# 39-996_-_SM_Clock-Timer.net
KiCad netlist of a schematic drawn in Altium Designer
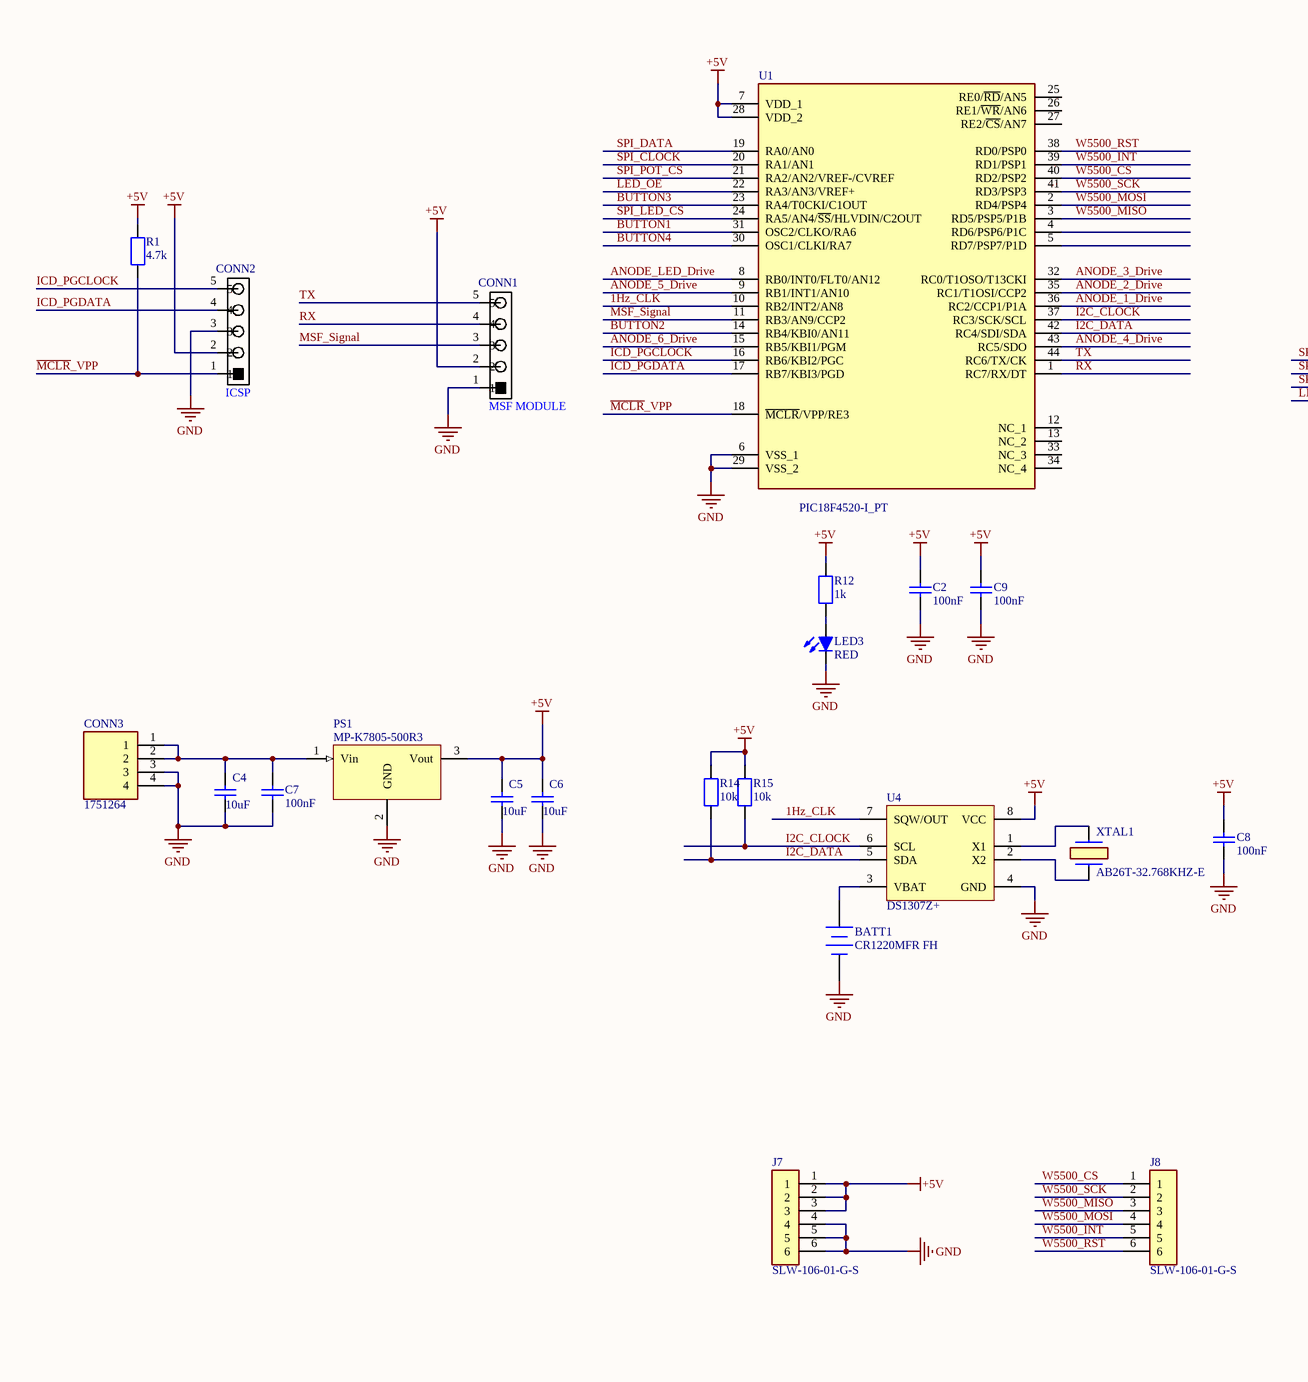
[diagram p0: 39-996 - SM Clock-Timer.SchDoc, left]
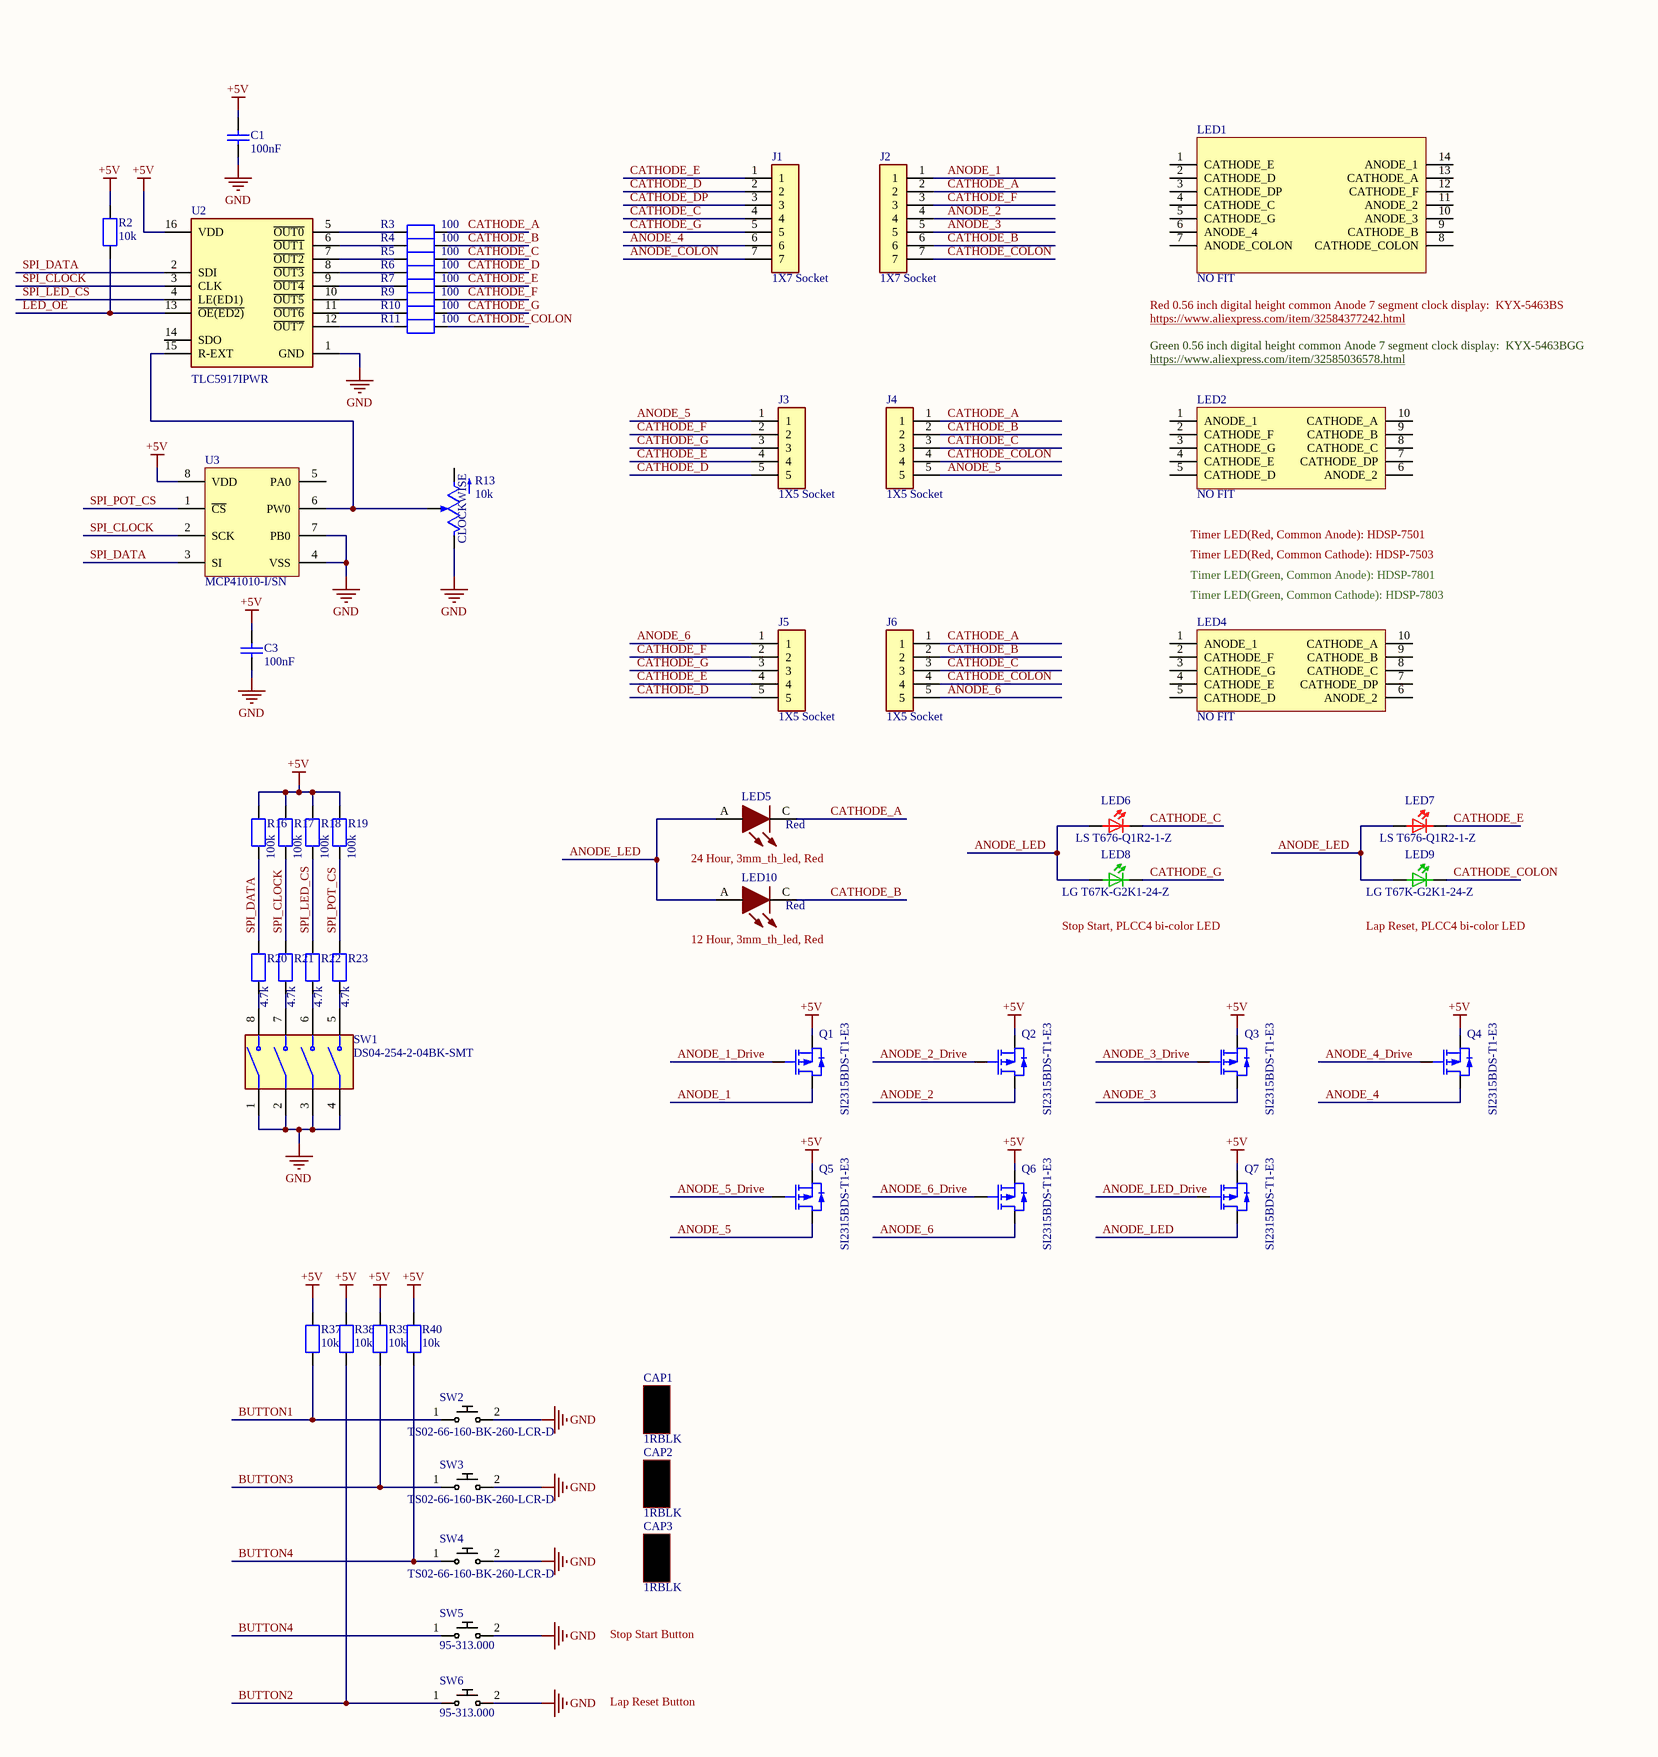
[diagram p1: 39-996 - SM Clock-Timer.SchDoc, right]

(export (version "E")
  (design (tool "Eeschema 10.0.6"))
  (components
    (comp (ref "BATT1")
      (value "CR1220MFR FH")
      (footprint "CR1220MFRFH")
      (description "Coin Cell Battery 3V2-PINHORZ40mAh")
      (fields (field (name "MANUFACTURER") "Renata"))
      (libsource (lib "SM Desk Clock-Timer") (part "CR1220MFR FH"))
    )
    (comp (ref "C1")
      (value "100nF")
      (footprint "C0603")
      (description "100nF ± 10% 50V")
      (fields
        (field (name "MANUFACTURER") "Yageo")
        (field (name "MANUFACTURER PART NUMBER") "CC0603KRX7R9BB104")
      )
      (libsource (lib "Cue Light Output PCB - RJ45") (part "100nF ± 10% 50V"))
    )
    (comp (ref "C2")
      (value "100nF")
      (footprint "C0603")
      (description "100nF ± 10% 50V")
      (fields
        (field (name "MANUFACTURER") "Yageo")
        (field (name "MANUFACTURER PART NUMBER") "CC0603KRX7R9BB104")
      )
      (libsource (lib "Cue Light Output PCB - RJ45") (part "100nF ± 10% 50V"))
    )
    (comp (ref "C3")
      (value "100nF")
      (footprint "C0603")
      (description "100nF ± 10% 50V")
      (fields
        (field (name "MANUFACTURER") "Yageo")
        (field (name "MANUFACTURER PART NUMBER") "CC0603KRX7R9BB104")
      )
      (libsource (lib "Cue Light Output PCB - RJ45") (part "100nF ± 10% 50V"))
    )
    (comp (ref "C4")
      (value "10uF")
      (footprint "C1206")
      (description "10uF ± 10% 50V")
      (fields
        (field (name "MANUFACTURER") "Murata")
        (field (name "MANUFACTURER PART NUMBER") "GRT31CR61H106KE01L")
      )
      (libsource (lib "Cue Light Output PCB - RJ45") (part "10uF ± 10% 50V"))
    )
    (comp (ref "C5")
      (value "10uF")
      (footprint "C1206")
      (description "10uF ± 10% 50V")
      (fields
        (field (name "MANUFACTURER") "Murata")
        (field (name "MANUFACTURER PART NUMBER") "GRT31CR61H106KE01L")
      )
      (libsource (lib "Cue Light Output PCB - RJ45") (part "10uF ± 10% 50V"))
    )
    (comp (ref "C6")
      (value "10uF")
      (footprint "C1206")
      (description "10uF ± 10% 50V")
      (fields
        (field (name "MANUFACTURER") "Murata")
        (field (name "MANUFACTURER PART NUMBER") "GRT31CR61H106KE01L")
      )
      (libsource (lib "Cue Light Output PCB - RJ45") (part "10uF ± 10% 50V"))
    )
    (comp (ref "C7")
      (value "100nF")
      (footprint "C0603")
      (description "100nF ± 10% 50V")
      (fields
        (field (name "MANUFACTURER") "Yageo")
        (field (name "MANUFACTURER PART NUMBER") "CC0603KRX7R9BB104")
      )
      (libsource (lib "Cue Light Output PCB - RJ45") (part "100nF ± 10% 50V"))
    )
    (comp (ref "C8")
      (value "100nF")
      (footprint "C0603")
      (description "100nF ± 10% 50V")
      (fields
        (field (name "MANUFACTURER") "Yageo")
        (field (name "MANUFACTURER PART NUMBER") "CC0603KRX7R9BB104")
      )
      (libsource (lib "Cue Light Output PCB - RJ45") (part "100nF ± 10% 50V"))
    )
    (comp (ref "C9")
      (value "100nF")
      (footprint "C0603")
      (description "100nF ± 10% 50V")
      (fields
        (field (name "MANUFACTURER") "Yageo")
        (field (name "MANUFACTURER PART NUMBER") "CC0603KRX7R9BB104")
      )
      (libsource (lib "Cue Light Output PCB - RJ45") (part "100nF ± 10% 50V"))
    )
    (comp (ref "CAP1")
      (value "1RBLK")
      (footprint "1RBLK")
      (description "Switch Bezels / Switch Caps 9 X 5MM RND CAP BLK")
      (fields (field (name "MANUFACTURER") "E-Switch"))
      (libsource (lib "SM Desk Clock-Timer") (part "1RBLK"))
    )
    (comp (ref "CAP2")
      (value "1RBLK")
      (footprint "1RBLK")
      (description "Switch Bezels / Switch Caps 9 X 5MM RND CAP BLK")
      (fields (field (name "MANUFACTURER") "E-Switch"))
      (libsource (lib "SM Desk Clock-Timer") (part "1RBLK"))
    )
    (comp (ref "CAP3")
      (value "1RBLK")
      (footprint "1RBLK")
      (description "Switch Bezels / Switch Caps 9 X 5MM RND CAP BLK")
      (fields (field (name "MANUFACTURER") "E-Switch"))
      (libsource (lib "SM Desk Clock-Timer") (part "1RBLK"))
    )
    (comp (ref "CONN1")
      (value "NO FIT")
      (footprint "ICSP")
      (description "ICSP Header - 5 Pin, 2.54mm Pitch")
      (libsource (lib "GDS_CONN") (part "ICSP"))
    )
    (comp (ref "CONN2")
      (value "NO FIT")
      (footprint "ICSP")
      (description "ICSP Header - 5 Pin, 2.54mm Pitch")
      (libsource (lib "GDS_CONN") (part "ICSP"))
    )
    (comp (ref "CONN3")
      (value "1751264")
      (footprint "1751264")
      (description "Fixed Terminal Blocks 4P 3.5mm 90DEG")
      (fields (field (name "MANUFACTURER") "Phoenix Contact"))
      (libsource (lib "1751264") (part "1751264"))
    )
    (comp (ref "J1")
      (value "1X7 Socket")
      (footprint "D019970742")
      (description "IC & Component Sockets 7 WAY SIL VERT SKT")
      (fields (field (name "MANUFACTURER") "Harwin") (field (name "MANUFACTURER PART NUMBER") "D01-9970742"))
      (libsource (lib "") (part "D01-9970742_1"))
    )
    (comp (ref "J2")
      (value "1X7 Socket")
      (footprint "D019970742")
      (description "IC & Component Sockets 7 WAY SIL VERT SKT")
      (fields (field (name "MANUFACTURER") "Harwin") (field (name "MANUFACTURER PART NUMBER") "D01-9970742"))
      (libsource (lib "SM Desk Clock-Timer") (part "D01-9970742"))
    )
    (comp (ref "J3")
      (value "1X5 Socket")
      (footprint "D01-9970542")
      (description "IC & Component Sockets 5 WAY SIL VERT SKT")
      (fields (field (name "MANUFACTURER") "Harwin") (field (name "MANUFACTURER PART NUMBER") "D01-9970542"))
      (libsource (lib "SM Desk Clock-Timer") (part "D01-9970542"))
    )
    (comp (ref "J4")
      (value "1X5 Socket")
      (footprint "D01-9970542")
      (description "IC & Component Sockets 5 WAY SIL VERT SKT")
      (fields (field (name "MANUFACTURER") "Harwin") (field (name "MANUFACTURER PART NUMBER") "D01-9970542"))
      (libsource (lib "") (part "D01-9970542_1"))
    )
    (comp (ref "J5")
      (value "1X5 Socket")
      (footprint "D01-9970542")
      (description "IC & Component Sockets 5 WAY SIL VERT SKT")
      (fields (field (name "MANUFACTURER") "Harwin") (field (name "MANUFACTURER PART NUMBER") "D01-9970542"))
      (libsource (lib "SM Desk Clock-Timer") (part "D01-9970542"))
    )
    (comp (ref "J6")
      (value "1X5 Socket")
      (footprint "D01-9970542")
      (description "IC & Component Sockets 5 WAY SIL VERT SKT")
      (fields (field (name "MANUFACTURER") "Harwin") (field (name "MANUFACTURER PART NUMBER") "D01-9970542"))
      (libsource (lib "") (part "D01-9970542_1"))
    )
    (comp (ref "J7")
      (value "SLW-106-01-G-S")
      (footprint "SLW-106-01-G-S")
      (description "Headers & Wire Housings .100\" Tiger Buy Low Profile Socket Strip")
      (fields (field (name "MANUFACTURER") "Samtec"))
      (libsource (lib "SM Desk Clock-Timer") (part "SLW-106-01-G-S"))
    )
    (comp (ref "J8")
      (value "SLW-106-01-G-S")
      (footprint "SLW-106-01-G-S")
      (description "Headers & Wire Housings .100\" Tiger Buy Low Profile Socket Strip")
      (fields (field (name "MANUFACTURER") "Samtec"))
      (libsource (lib "") (part "SLW-106-01-G-S_1"))
    )
    (comp (ref "LED1")
      (value "NO FIT")
      (footprint "Common Cathode 7 Segment Clock Display")
      (description "0.56 inch digit height common Anode 7 segment clock display")
      (libsource (lib "SM Desk Clock-Timer") (part "Common Anode 7 Segment Clock Display"))
    )
    (comp (ref "LED2")
      (value "NO FIT")
      (footprint "HDSP7501")
      (description "7 SEG NUMERIC DISPLAY, HIGH EFFICIENCY RED, 7.6 mm")
      (fields
        (field (name "MANUFACTURER") "Avago Technologies")
        (field (name "MANUFACTURER PART NUMBER") "HDSP-7501")
      )
      (libsource (lib "SM Desk Clock-Timer") (part "HDSP-7501"))
    )
    (comp (ref "LED3")
      (value "RED")
      (footprint "LED_PLCC2")
      (description "Standard LEDs - SMD Super Red, 645nm 180mcd, 20mA")
      (fields
        (field (name "MANUFACTURER") "ams OSRAM")
        (field (name "MANUFACTURER PART NUMBER") "LS T676-Q1R2-1-Z")
      )
      (libsource (lib "Cue Light Output PCB - RJ45") (part "LS T676-Q1R2-1-Z"))
    )
    (comp (ref "LED4")
      (value "NO FIT")
      (footprint "HDSP7501")
      (description "7 SEG NUMERIC DISPLAY, HIGH EFFICIENCY RED, 7.6 mm")
      (fields
        (field (name "MANUFACTURER") "Avago Technologies")
        (field (name "MANUFACTURER PART NUMBER") "HDSP-7501")
      )
      (libsource (lib "SM Desk Clock-Timer") (part "HDSP-7501"))
    )
    (comp (ref "LED5")
      (value "Red")
      (footprint "LED_3mm")
      (description "Standard LEDs - Through Hole RED DIFFUSED")
      (fields (field (name "MANUFACTURER") "Kingbright") (field (name "MANUFACTURER PART NUMBER") "WP132XID"))
      (libsource (lib "SM Desk Clock-Timer") (part "WP132XID"))
    )
    (comp (ref "LED6")
      (value "LS T676-Q1R2-1-Z")
      (footprint "PLCC-2")
      (description "Standard LEDs - SMD Super Red, 645nm 180mcd, 20mA")
      (fields (field (name "MANUFACTURER") "ams OSRAM"))
      (libsource (lib "47-538 - Desk Power CTRL Button") (part "LS T676-Q1R2-1-Z"))
    )
    (comp (ref "LED7")
      (value "LS T676-Q1R2-1-Z")
      (footprint "PLCC-2")
      (description "Standard LEDs - SMD Super Red, 645nm 180mcd, 20mA")
      (fields (field (name "MANUFACTURER") "ams OSRAM"))
      (libsource (lib "47-538 - Desk Power CTRL Button") (part "LS T676-Q1R2-1-Z"))
    )
    (comp (ref "LED8")
      (value "LG T67K-G2K1-24-Z")
      (footprint "PLCC-2")
      (description "Standard LEDs - SMD Green 570nm, 20mA")
      (fields (field (name "MANUFACTURER") "ams OSRAM"))
      (libsource (lib "47-538 - Desk Power CTRL Button") (part "LG T67K-G2K1-24-Z"))
    )
    (comp (ref "LED9")
      (value "LG T67K-G2K1-24-Z")
      (footprint "PLCC-2")
      (description "Standard LEDs - SMD Green 570nm, 20mA")
      (fields (field (name "MANUFACTURER") "ams OSRAM"))
      (libsource (lib "47-538 - Desk Power CTRL Button") (part "LG T67K-G2K1-24-Z"))
    )
    (comp (ref "LED10")
      (value "Red")
      (footprint "LED_3mm")
      (description "Standard LEDs - Through Hole RED DIFFUSED")
      (fields (field (name "MANUFACTURER") "Kingbright") (field (name "MANUFACTURER PART NUMBER") "WP132XID"))
      (libsource (lib "SM Desk Clock-Timer") (part "WP132XID"))
    )
    (comp (ref "PS1")
      (value "MP-K7805-500R3")
      (footprint "CONV_K7805-500R3")
      (fields (field (name "MANUFACTURER") "MULTICOMP PRO"))
      (libsource (lib "SM Desk Clock-Timer") (part "MP-K7805-500R3"))
    )
    (comp (ref "Q1")
      (value "SI2315BDS-T1-E3")
      (footprint "SOT23-3")
      (description "MOSFET 1.8V 3.2A 1.25W")
      (fields (field (name "MANUFACTURER") "Vishay Semiconductors"))
      (libsource (lib "SM Desk Clock-Timer") (part "SI2315BDS-T1-E3"))
    )
    (comp (ref "Q2")
      (value "SI2315BDS-T1-E3")
      (footprint "SOT23-3")
      (description "MOSFET 1.8V 3.2A 1.25W")
      (fields (field (name "MANUFACTURER") "Vishay Semiconductors"))
      (libsource (lib "SM Desk Clock-Timer") (part "SI2315BDS-T1-E3"))
    )
    (comp (ref "Q3")
      (value "SI2315BDS-T1-E3")
      (footprint "SOT23-3")
      (description "MOSFET 1.8V 3.2A 1.25W")
      (fields (field (name "MANUFACTURER") "Vishay Semiconductors"))
      (libsource (lib "SM Desk Clock-Timer") (part "SI2315BDS-T1-E3"))
    )
    (comp (ref "Q4")
      (value "SI2315BDS-T1-E3")
      (footprint "SOT23-3")
      (description "MOSFET 1.8V 3.2A 1.25W")
      (fields (field (name "MANUFACTURER") "Vishay Semiconductors"))
      (libsource (lib "SM Desk Clock-Timer") (part "SI2315BDS-T1-E3"))
    )
    (comp (ref "Q5")
      (value "SI2315BDS-T1-E3")
      (footprint "SOT23-3")
      (description "MOSFET 1.8V 3.2A 1.25W")
      (fields (field (name "MANUFACTURER") "Vishay Semiconductors"))
      (libsource (lib "SM Desk Clock-Timer") (part "SI2315BDS-T1-E3"))
    )
    (comp (ref "Q6")
      (value "SI2315BDS-T1-E3")
      (footprint "SOT23-3")
      (description "MOSFET 1.8V 3.2A 1.25W")
      (fields (field (name "MANUFACTURER") "Vishay Semiconductors"))
      (libsource (lib "SM Desk Clock-Timer") (part "SI2315BDS-T1-E3"))
    )
    (comp (ref "Q7")
      (value "SI2315BDS-T1-E3")
      (footprint "SOT23-3")
      (description "MOSFET 1.8V 3.2A 1.25W")
      (fields (field (name "MANUFACTURER") "Vishay Semiconductors"))
      (libsource (lib "SM Desk Clock-Timer") (part "SI2315BDS-T1-E3"))
    )
    (comp (ref "R1")
      (value "4.7k")
      (footprint "R0603")
      (description "4.7 kOhms ±1% 0.1W")
      (fields
        (field (name "MANUFACTURER") "Yageo")
        (field (name "MANUFACTURER PART NUMBER") "RC0603FR-074K7L")
      )
      (libsource (lib "32-503 - DriveHUB - 1Ch 10A Variable CV") (part "4.7 kOhms ±1% 0.1W"))
    )
    (comp (ref "R2")
      (value "10k")
      (footprint "R0603")
      (description "10 kOhms ±1% 0.1W")
      (fields
        (field (name "MANUFACTURER") "Yageo")
        (field (name "MANUFACTURER PART NUMBER") "RC0603FR-0710KL")
      )
      (libsource (lib "SM Desk Clock-Timer") (part "10 kOhms ±1% 0.1W"))
    )
    (comp (ref "R3")
      (value "100")
      (footprint "R0603")
      (description "100 Ohms ±1% 0.1W")
      (fields
        (field (name "MANUFACTURER") "Yageo")
        (field (name "MANUFACTURER PART NUMBER") "RC0603FR-07100RL")
      )
      (libsource (lib "SM Desk Clock-Timer") (part "100 Ohms ±1% 0.1W"))
    )
    (comp (ref "R4")
      (value "100")
      (footprint "R0603")
      (description "100 Ohms ±1% 0.1W")
      (fields
        (field (name "MANUFACTURER") "Yageo")
        (field (name "MANUFACTURER PART NUMBER") "RC0603FR-07100RL")
      )
      (libsource (lib "SM Desk Clock-Timer") (part "100 Ohms ±1% 0.1W"))
    )
    (comp (ref "R5")
      (value "100")
      (footprint "R0603")
      (description "100 Ohms ±1% 0.1W")
      (fields
        (field (name "MANUFACTURER") "Yageo")
        (field (name "MANUFACTURER PART NUMBER") "RC0603FR-07100RL")
      )
      (libsource (lib "SM Desk Clock-Timer") (part "100 Ohms ±1% 0.1W"))
    )
    (comp (ref "R6")
      (value "100")
      (footprint "R0603")
      (description "100 Ohms ±1% 0.1W")
      (fields
        (field (name "MANUFACTURER") "Yageo")
        (field (name "MANUFACTURER PART NUMBER") "RC0603FR-07100RL")
      )
      (libsource (lib "SM Desk Clock-Timer") (part "100 Ohms ±1% 0.1W"))
    )
    (comp (ref "R7")
      (value "100")
      (footprint "R0603")
      (description "100 Ohms ±1% 0.1W")
      (fields
        (field (name "MANUFACTURER") "Yageo")
        (field (name "MANUFACTURER PART NUMBER") "RC0603FR-07100RL")
      )
      (libsource (lib "SM Desk Clock-Timer") (part "100 Ohms ±1% 0.1W"))
    )
    (comp (ref "R9")
      (value "100")
      (footprint "R0603")
      (description "100 Ohms ±1% 0.1W")
      (fields
        (field (name "MANUFACTURER") "Yageo")
        (field (name "MANUFACTURER PART NUMBER") "RC0603FR-07100RL")
      )
      (libsource (lib "SM Desk Clock-Timer") (part "100 Ohms ±1% 0.1W"))
    )
    (comp (ref "R10")
      (value "100")
      (footprint "R0603")
      (description "100 Ohms ±1% 0.1W")
      (fields
        (field (name "MANUFACTURER") "Yageo")
        (field (name "MANUFACTURER PART NUMBER") "RC0603FR-07100RL")
      )
      (libsource (lib "SM Desk Clock-Timer") (part "100 Ohms ±1% 0.1W"))
    )
    (comp (ref "R11")
      (value "100")
      (footprint "R0603")
      (description "100 Ohms ±1% 0.1W")
      (fields
        (field (name "MANUFACTURER") "Yageo")
        (field (name "MANUFACTURER PART NUMBER") "RC0603FR-07100RL")
      )
      (libsource (lib "SM Desk Clock-Timer") (part "100 Ohms ±1% 0.1W"))
    )
    (comp (ref "R12")
      (value "1k")
      (footprint "R0603")
      (description "1 kOhms ±1% 0.1W")
      (fields
        (field (name "MANUFACTURER") "Yageo")
        (field (name "MANUFACTURER PART NUMBER") "RC0603FR-071KL")
      )
      (libsource (lib "SM Desk Clock-Timer") (part "1 kOhms ±1% 0.1W"))
    )
    (comp (ref "R13")
      (value "10k")
      (footprint "TRIM_3386F-1-103LF")
      (description "Trimmer Resistors - Through Hole 3/8\" 10Kohms 10% 0.5Watts Square")
      (fields
        (field (name "MANUFACTURER") "Bourns")
        (field (name "MANUFACTURER PART NUMBER") "3386F-1-103LF")
      )
      (libsource (lib "SM Desk Clock-Timer") (part "3386F-1-103LF"))
    )
    (comp (ref "R14")
      (value "10k")
      (footprint "R0603")
      (description "10 kOhms ±1% 0.1W")
      (fields
        (field (name "MANUFACTURER") "Yageo")
        (field (name "MANUFACTURER PART NUMBER") "RC0603FR-0710KL")
      )
      (libsource (lib "SM Desk Clock-Timer") (part "10 kOhms ±1% 0.1W"))
    )
    (comp (ref "R15")
      (value "10k")
      (footprint "R0603")
      (description "10 kOhms ±1% 0.1W")
      (fields
        (field (name "MANUFACTURER") "Yageo")
        (field (name "MANUFACTURER PART NUMBER") "RC0603FR-0710KL")
      )
      (libsource (lib "SM Desk Clock-Timer") (part "10 kOhms ±1% 0.1W"))
    )
    (comp (ref "R16")
      (value "100k")
      (footprint "R0603")
      (description "100 kOhms ±1% 0.1W")
      (fields
        (field (name "MANUFACTURER") "Yageo")
        (field (name "MANUFACTURER PART NUMBER") "RC0603FR-07100KL")
      )
      (libsource (lib "SM Desk Clock-Timer") (part "100 kOhms ±1% 0.1W"))
    )
    (comp (ref "R17")
      (value "100k")
      (footprint "R0603")
      (description "100 kOhms ±1% 0.1W")
      (fields
        (field (name "MANUFACTURER") "Yageo")
        (field (name "MANUFACTURER PART NUMBER") "RC0603FR-07100KL")
      )
      (libsource (lib "SM Desk Clock-Timer") (part "100 kOhms ±1% 0.1W"))
    )
    (comp (ref "R18")
      (value "100k")
      (footprint "R0603")
      (description "100 kOhms ±1% 0.1W")
      (fields
        (field (name "MANUFACTURER") "Yageo")
        (field (name "MANUFACTURER PART NUMBER") "RC0603FR-07100KL")
      )
      (libsource (lib "SM Desk Clock-Timer") (part "100 kOhms ±1% 0.1W"))
    )
    (comp (ref "R19")
      (value "100k")
      (footprint "R0603")
      (description "100 kOhms ±1% 0.1W")
      (fields
        (field (name "MANUFACTURER") "Yageo")
        (field (name "MANUFACTURER PART NUMBER") "RC0603FR-07100KL")
      )
      (libsource (lib "SM Desk Clock-Timer") (part "100 kOhms ±1% 0.1W"))
    )
    (comp (ref "R20")
      (value "4.7k")
      (footprint "R0603")
      (description "4.7 kOhms ±1% 0.1W")
      (fields
        (field (name "MANUFACTURER") "Yageo")
        (field (name "MANUFACTURER PART NUMBER") "RC0603FR-074K7L")
      )
      (libsource (lib "32-503 - DriveHUB - 1Ch 10A Variable CV") (part "4.7 kOhms ±1% 0.1W"))
    )
    (comp (ref "R21")
      (value "4.7k")
      (footprint "R0603")
      (description "4.7 kOhms ±1% 0.1W")
      (fields
        (field (name "MANUFACTURER") "Yageo")
        (field (name "MANUFACTURER PART NUMBER") "RC0603FR-074K7L")
      )
      (libsource (lib "32-503 - DriveHUB - 1Ch 10A Variable CV") (part "4.7 kOhms ±1% 0.1W"))
    )
    (comp (ref "R22")
      (value "4.7k")
      (footprint "R0603")
      (description "4.7 kOhms ±1% 0.1W")
      (fields
        (field (name "MANUFACTURER") "Yageo")
        (field (name "MANUFACTURER PART NUMBER") "RC0603FR-074K7L")
      )
      (libsource (lib "32-503 - DriveHUB - 1Ch 10A Variable CV") (part "4.7 kOhms ±1% 0.1W"))
    )
    (comp (ref "R23")
      (value "4.7k")
      (footprint "R0603")
      (description "4.7 kOhms ±1% 0.1W")
      (fields
        (field (name "MANUFACTURER") "Yageo")
        (field (name "MANUFACTURER PART NUMBER") "RC0603FR-074K7L")
      )
      (libsource (lib "32-503 - DriveHUB - 1Ch 10A Variable CV") (part "4.7 kOhms ±1% 0.1W"))
    )
    (comp (ref "R37")
      (value "10k")
      (footprint "R0603")
      (description "10 kOhms ±1% 0.1W")
      (fields
        (field (name "MANUFACTURER") "Yageo")
        (field (name "MANUFACTURER PART NUMBER") "RC0603FR-0710KL")
      )
      (libsource (lib "SM Desk Clock-Timer") (part "10 kOhms ±1% 0.1W"))
    )
    (comp (ref "R38")
      (value "10k")
      (footprint "R0603")
      (description "10 kOhms ±1% 0.1W")
      (fields
        (field (name "MANUFACTURER") "Yageo")
        (field (name "MANUFACTURER PART NUMBER") "RC0603FR-0710KL")
      )
      (libsource (lib "SM Desk Clock-Timer") (part "10 kOhms ±1% 0.1W"))
    )
    (comp (ref "R39")
      (value "10k")
      (footprint "R0603")
      (description "10 kOhms ±1% 0.1W")
      (fields
        (field (name "MANUFACTURER") "Yageo")
        (field (name "MANUFACTURER PART NUMBER") "RC0603FR-0710KL")
      )
      (libsource (lib "SM Desk Clock-Timer") (part "10 kOhms ±1% 0.1W"))
    )
    (comp (ref "R40")
      (value "10k")
      (footprint "R0603")
      (description "10 kOhms ±1% 0.1W")
      (fields
        (field (name "MANUFACTURER") "Yageo")
        (field (name "MANUFACTURER PART NUMBER") "RC0603FR-0710KL")
      )
      (libsource (lib "SM Desk Clock-Timer") (part "10 kOhms ±1% 0.1W"))
    )
    (comp (ref "SW1")
      (value "DS04-254-2-04BK-SMT")
      (footprint "SW_DS04-254-2-04BK-SMT")
      (description "DIP Switches/SIP Switches DIP Switch, SPST, 2.54 pitch, flat actuator, SMT, 4 position, Black")
      (fields (field (name "MANUFACTURER") "CUI Devices"))
      (libsource (lib "SM Desk Clock-Timer") (part "DS04-254-2-04BK-SMT"))
    )
    (comp (ref "SW2")
      (value "TS02-66-160-BK-260-LCR-D")
      (footprint "SW_TS02-66-160-BK-260-LCR-D")
      (description "Tactile Switches 6 x 6 mm, 16 mm Act Height, 260 gf, Black, Long Crimped, Through Hole, SPST,")
      (fields (field (name "MANUFACTURER") "CUI Devices"))
      (libsource (lib "SM Desk Clock-Timer") (part "TS02-66-160-BK-260-LCR-D"))
    )
    (comp (ref "SW3")
      (value "TS02-66-160-BK-260-LCR-D")
      (footprint "SW_TS02-66-160-BK-260-LCR-D")
      (description "Tactile Switches 6 x 6 mm, 16 mm Act Height, 260 gf, Black, Long Crimped, Through Hole, SPST,")
      (fields (field (name "MANUFACTURER") "CUI Devices"))
      (libsource (lib "SM Desk Clock-Timer") (part "TS02-66-160-BK-260-LCR-D"))
    )
    (comp (ref "SW4")
      (value "TS02-66-160-BK-260-LCR-D")
      (footprint "SW_TS02-66-160-BK-260-LCR-D")
      (description "Tactile Switches 6 x 6 mm, 16 mm Act Height, 260 gf, Black, Long Crimped, Through Hole, SPST,")
      (fields (field (name "MANUFACTURER") "CUI Devices"))
      (libsource (lib "SM Desk Clock-Timer") (part "TS02-66-160-BK-260-LCR-D"))
    )
    (comp (ref "SW5")
      (value "95-313.000")
      (footprint "PUSHBUTTON_95-313.000")
      (description "Switching element square, 12.7 x 12.7 mm")
      (fields (field (name "MANUFACTURER") "eao"))
      (libsource (lib "47-538 - Desk Power CTRL Button") (part "95-313.000"))
    )
    (comp (ref "SW6")
      (value "95-313.000")
      (footprint "PUSHBUTTON_95-313.000")
      (description "Switching element square, 12.7 x 12.7 mm")
      (fields (field (name "MANUFACTURER") "eao"))
      (libsource (lib "47-538 - Desk Power CTRL Button") (part "95-313.000"))
    )
    (comp (ref "U1")
      (value "PIC18F4520-I_PT")
      (footprint "TQFP-44")
      (description "MCU 32 KB Flash,1536 RAM, 36 I/O")
      (fields
        (field (name "MANUFACTURER") "Microchip")
        (field (name "MANUFACTURER PART NUMBER") "PIC18F4520-I/PT")
      )
      (libsource (lib "SM Desk Clock-Timer") (part "PIC18F4520-I_PT"))
    )
    (comp (ref "U2")
      (value "TLC5917IPWR")
      (footprint "SOIC-16")
      (description "LED Lighting Drivers 8B Constant-Current LED Sink")
      (fields (field (name "MANUFACTURER") "Texas Instruments"))
      (libsource (lib "SM Desk Clock-Timer") (part "TLC5917IPWR"))
    )
    (comp (ref "U3")
      (value "MCP41010-I/SN")
      (footprint "SOIC-8")
      (description "Digital Potentiometer 10K 256pos SPI SO8")
      (fields (field (name "MANUFACTURER") "Microchip"))
      (libsource (lib "SM Desk Clock-Timer") (part "MCP41010-I/SN"))
    )
    (comp (ref "U4")
      (value "DS1307Z+")
      (footprint "SOIC-8")
      (description "DS1307Z+, Real Time Clock, Alarm, Calendar, Clock, 56B RAM, I2C, 5V, 8-Pin SOIC")
      (fields (field (name "MANUFACTURER") "Analog Devices"))
      (libsource (lib "SM Desk Clock-Timer") (part "DS1307Z+"))
    )
    (comp (ref "XTAL1")
      (value "AB26T-32.768KHZ-E")
      (footprint "AB26T32768KHZE")
      (description "OSC XO 1.33GHZ 2.5V LVPECL")
      (fields (field (name "MANUFACTURER") "ABRACON"))
      (libsource (lib "SM Desk Clock-Timer") (part "AB26T-32.768KHZ-E"))
    )
  )
  (nets
    (net (code "1") (name "+5V") (class "Default")
      (node (ref "C1") (pin "2") (pinfunction "2_2") (pintype "passive"))
      (node (ref "C2") (pin "2") (pinfunction "2_2") (pintype "passive"))
      (node (ref "C3") (pin "2") (pinfunction "2_2") (pintype "passive"))
      (node (ref "C5") (pin "2") (pinfunction "2_2") (pintype "passive"))
      (node (ref "C6") (pin "2") (pinfunction "2_2") (pintype "passive"))
      (node (ref "C8") (pin "2") (pinfunction "2_2") (pintype "passive"))
      (node (ref "C9") (pin "2") (pinfunction "2_2") (pintype "passive"))
      (node (ref "CONN1") (pin "2") (pinfunction "2_2") (pintype "passive"))
      (node (ref "CONN2") (pin "2") (pinfunction "2_2") (pintype "passive"))
      (node (ref "J7") (pin "1") (pinfunction "1_1") (pintype "passive"))
      (node (ref "J7") (pin "2") (pinfunction "2_2") (pintype "passive"))
      (node (ref "J7") (pin "3") (pinfunction "3_3") (pintype "passive"))
      (node (ref "PS1") (pin "3") (pinfunction "Vout_3") (pintype "passive"))
      (node (ref "Q1") (pin "2") (pinfunction "S_2") (pintype "passive"))
      (node (ref "Q2") (pin "2") (pinfunction "S_2") (pintype "passive"))
      (node (ref "Q3") (pin "2") (pinfunction "S_2") (pintype "passive"))
      (node (ref "Q4") (pin "2") (pinfunction "S_2") (pintype "passive"))
      (node (ref "Q5") (pin "2") (pinfunction "S_2") (pintype "passive"))
      (node (ref "Q6") (pin "2") (pinfunction "S_2") (pintype "passive"))
      (node (ref "Q7") (pin "2") (pinfunction "S_2") (pintype "passive"))
      (node (ref "R1") (pin "2") (pinfunction "2_2") (pintype "passive"))
      (node (ref "R12") (pin "2") (pinfunction "2_2") (pintype "passive"))
      (node (ref "R14") (pin "2") (pinfunction "2_2") (pintype "passive"))
      (node (ref "R15") (pin "2") (pinfunction "2_2") (pintype "passive"))
      (node (ref "R16") (pin "2") (pinfunction "2_2") (pintype "passive"))
      (node (ref "R17") (pin "2") (pinfunction "2_2") (pintype "passive"))
      (node (ref "R18") (pin "2") (pinfunction "2_2") (pintype "passive"))
      (node (ref "R19") (pin "2") (pinfunction "2_2") (pintype "passive"))
      (node (ref "R2") (pin "2") (pinfunction "2_2") (pintype "passive"))
      (node (ref "R37") (pin "2") (pinfunction "2_2") (pintype "passive"))
      (node (ref "R38") (pin "2") (pinfunction "2_2") (pintype "passive"))
      (node (ref "R39") (pin "2") (pinfunction "2_2") (pintype "passive"))
      (node (ref "R40") (pin "2") (pinfunction "2_2") (pintype "passive"))
      (node (ref "U1") (pin "28") (pinfunction "VDD_2_28") (pintype "passive"))
      (node (ref "U1") (pin "7") (pinfunction "VDD_1_7") (pintype "passive"))
      (node (ref "U2") (pin "16") (pinfunction "VDD_16") (pintype "passive"))
      (node (ref "U3") (pin "8") (pinfunction "VDD_8") (pintype "passive"))
      (node (ref "U4") (pin "8") (pinfunction "VCC_8") (pintype "passive"))
    )
    (net (code "2") (name "/1Hz_CLK") (class "Default")
      (node (ref "U1") (pin "10") (pinfunction "RB2/INT2/AN8_10") (pintype "passive"))
      (node (ref "U4") (pin "7") (pinfunction "SQW/OUT_7") (pintype "passive"))
    )
    (net (code "3") (name "/ANODE_1") (class "Default")
      (node (ref "J2") (pin "1") (pinfunction "1_1") (pintype "passive"))
      (node (ref "Q1") (pin "3") (pinfunction "D_3") (pintype "passive"))
    )
    (net (code "4") (name "/ANODE_1_Drive") (class "Default")
      (node (ref "Q1") (pin "1") (pinfunction "G_1") (pintype "passive"))
      (node (ref "U1") (pin "36") (pinfunction "RC2/CCP1/P1A_36") (pintype "passive"))
    )
    (net (code "5") (name "/ANODE_2") (class "Default")
      (node (ref "J2") (pin "4") (pinfunction "4_4") (pintype "passive"))
      (node (ref "Q2") (pin "3") (pinfunction "D_3") (pintype "passive"))
    )
    (net (code "6") (name "/ANODE_2_Drive") (class "Default")
      (node (ref "Q2") (pin "1") (pinfunction "G_1") (pintype "passive"))
      (node (ref "U1") (pin "35") (pinfunction "RC1/T1OSI/CCP2_35") (pintype "passive"))
    )
    (net (code "7") (name "/ANODE_3") (class "Default")
      (node (ref "J2") (pin "5") (pinfunction "5_5") (pintype "passive"))
      (node (ref "Q3") (pin "3") (pinfunction "D_3") (pintype "passive"))
    )
    (net (code "8") (name "/ANODE_3_Drive") (class "Default")
      (node (ref "Q3") (pin "1") (pinfunction "G_1") (pintype "passive"))
      (node (ref "U1") (pin "32") (pinfunction "RC0/T1OSO/T13CKI_32") (pintype "passive"))
    )
    (net (code "9") (name "/ANODE_4") (class "Default")
      (node (ref "J1") (pin "6") (pinfunction "6_6") (pintype "passive"))
      (node (ref "Q4") (pin "3") (pinfunction "D_3") (pintype "passive"))
    )
    (net (code "10") (name "/ANODE_4_Drive") (class "Default")
      (node (ref "Q4") (pin "1") (pinfunction "G_1") (pintype "passive"))
      (node (ref "U1") (pin "43") (pinfunction "RC5/SDO_43") (pintype "passive"))
    )
    (net (code "11") (name "/ANODE_5") (class "Default")
      (node (ref "J3") (pin "1") (pinfunction "1_1") (pintype "passive"))
      (node (ref "J4") (pin "5") (pinfunction "5_5") (pintype "passive"))
      (node (ref "Q5") (pin "3") (pinfunction "D_3") (pintype "passive"))
    )
    (net (code "12") (name "/ANODE_5_Drive") (class "Default")
      (node (ref "Q5") (pin "1") (pinfunction "G_1") (pintype "passive"))
      (node (ref "U1") (pin "9") (pinfunction "RB1/INT1/AN10_9") (pintype "passive"))
    )
    (net (code "13") (name "/ANODE_6") (class "Default")
      (node (ref "J5") (pin "1") (pinfunction "1_1") (pintype "passive"))
      (node (ref "J6") (pin "5") (pinfunction "5_5") (pintype "passive"))
      (node (ref "Q6") (pin "3") (pinfunction "D_3") (pintype "passive"))
    )
    (net (code "14") (name "/ANODE_6_Drive") (class "Default")
      (node (ref "Q6") (pin "1") (pinfunction "G_1") (pintype "passive"))
      (node (ref "U1") (pin "15") (pinfunction "RB5/KBI1/PGM_15") (pintype "passive"))
    )
    (net (code "15") (name "/ANODE_COLON") (class "Default")
      (node (ref "J1") (pin "7") (pinfunction "7_7") (pintype "passive"))
    )
    (net (code "16") (name "/ANODE_LED") (class "Default")
      (node (ref "LED10") (pin "A") (pinfunction "A_A") (pintype "passive"))
      (node (ref "LED5") (pin "A") (pinfunction "A_A") (pintype "passive"))
      (node (ref "LED6") (pin "A") (pinfunction "A_A") (pintype "passive"))
      (node (ref "LED7") (pin "A") (pinfunction "A_A") (pintype "passive"))
      (node (ref "LED8") (pin "A") (pinfunction "A_A") (pintype "passive"))
      (node (ref "LED9") (pin "A") (pinfunction "A_A") (pintype "passive"))
      (node (ref "Q7") (pin "3") (pinfunction "D_3") (pintype "passive"))
    )
    (net (code "17") (name "/ANODE_LED_Drive") (class "Default")
      (node (ref "Q7") (pin "1") (pinfunction "G_1") (pintype "passive"))
      (node (ref "U1") (pin "8") (pinfunction "RB0/INT0/FLT0/AN12_8") (pintype "passive"))
    )
    (net (code "18") (name "/BUTTON1") (class "Default")
      (node (ref "R37") (pin "1") (pinfunction "1_1") (pintype "passive"))
      (node (ref "SW2") (pin "1") (pinfunction "1_1") (pintype "passive"))
      (node (ref "U1") (pin "31") (pinfunction "OSC2/CLKO/RA6_31") (pintype "passive"))
    )
    (net (code "19") (name "/BUTTON2") (class "Default")
      (node (ref "R38") (pin "1") (pinfunction "1_1") (pintype "passive"))
      (node (ref "SW6") (pin "1") (pinfunction "1_1") (pintype "passive"))
      (node (ref "U1") (pin "14") (pinfunction "RB4/KBI0/AN11_14") (pintype "passive"))
    )
    (net (code "20") (name "/BUTTON3") (class "Default")
      (node (ref "R39") (pin "1") (pinfunction "1_1") (pintype "passive"))
      (node (ref "SW3") (pin "1") (pinfunction "1_1") (pintype "passive"))
      (node (ref "U1") (pin "23") (pinfunction "RA4/T0CKI/C1OUT_23") (pintype "passive"))
    )
    (net (code "21") (name "/BUTTON4") (class "Default")
      (node (ref "R40") (pin "1") (pinfunction "1_1") (pintype "passive"))
      (node (ref "SW4") (pin "1") (pinfunction "1_1") (pintype "passive"))
      (node (ref "SW5") (pin "1") (pinfunction "1_1") (pintype "passive"))
      (node (ref "U1") (pin "30") (pinfunction "OSC1/CLKI/RA7_30") (pintype "passive"))
    )
    (net (code "22") (name "/CATHODE_A") (class "Default")
      (node (ref "J2") (pin "2") (pinfunction "2_2") (pintype "passive"))
      (node (ref "J4") (pin "1") (pinfunction "1_1") (pintype "passive"))
      (node (ref "J6") (pin "1") (pinfunction "1_1") (pintype "passive"))
      (node (ref "LED5") (pin "C") (pinfunction "C_C") (pintype "passive"))
      (node (ref "R3") (pin "2") (pinfunction "2_2") (pintype "passive"))
    )
    (net (code "23") (name "/CATHODE_B") (class "Default")
      (node (ref "J2") (pin "6") (pinfunction "6_6") (pintype "passive"))
      (node (ref "J4") (pin "2") (pinfunction "2_2") (pintype "passive"))
      (node (ref "J6") (pin "2") (pinfunction "2_2") (pintype "passive"))
      (node (ref "LED10") (pin "C") (pinfunction "C_C") (pintype "passive"))
      (node (ref "R4") (pin "2") (pinfunction "2_2") (pintype "passive"))
    )
    (net (code "24") (name "/CATHODE_C") (class "Default")
      (node (ref "J1") (pin "4") (pinfunction "4_4") (pintype "passive"))
      (node (ref "J4") (pin "3") (pinfunction "3_3") (pintype "passive"))
      (node (ref "J6") (pin "3") (pinfunction "3_3") (pintype "passive"))
      (node (ref "LED6") (pin "C") (pinfunction "C_C") (pintype "passive"))
      (node (ref "R5") (pin "2") (pinfunction "2_2") (pintype "passive"))
    )
    (net (code "25") (name "/CATHODE_COLON") (class "Default")
      (node (ref "J2") (pin "7") (pinfunction "7_7") (pintype "passive"))
      (node (ref "J4") (pin "4") (pinfunction "4_4") (pintype "passive"))
      (node (ref "J6") (pin "4") (pinfunction "4_4") (pintype "passive"))
      (node (ref "LED9") (pin "C") (pinfunction "C_C") (pintype "passive"))
      (node (ref "R11") (pin "2") (pinfunction "2_2") (pintype "passive"))
    )
    (net (code "26") (name "/CATHODE_D") (class "Default")
      (node (ref "J1") (pin "2") (pinfunction "2_2") (pintype "passive"))
      (node (ref "J3") (pin "5") (pinfunction "5_5") (pintype "passive"))
      (node (ref "J5") (pin "5") (pinfunction "5_5") (pintype "passive"))
      (node (ref "R6") (pin "2") (pinfunction "2_2") (pintype "passive"))
    )
    (net (code "27") (name "/CATHODE_DP") (class "Default")
      (node (ref "J1") (pin "3") (pinfunction "3_3") (pintype "passive"))
    )
    (net (code "28") (name "/CATHODE_E") (class "Default")
      (node (ref "J1") (pin "1") (pinfunction "1_1") (pintype "passive"))
      (node (ref "J3") (pin "4") (pinfunction "4_4") (pintype "passive"))
      (node (ref "J5") (pin "4") (pinfunction "4_4") (pintype "passive"))
      (node (ref "LED7") (pin "C") (pinfunction "C_C") (pintype "passive"))
      (node (ref "R7") (pin "2") (pinfunction "2_2") (pintype "passive"))
    )
    (net (code "29") (name "/CATHODE_F") (class "Default")
      (node (ref "J2") (pin "3") (pinfunction "3_3") (pintype "passive"))
      (node (ref "J3") (pin "2") (pinfunction "2_2") (pintype "passive"))
      (node (ref "J5") (pin "2") (pinfunction "2_2") (pintype "passive"))
      (node (ref "R9") (pin "2") (pinfunction "2_2") (pintype "passive"))
    )
    (net (code "30") (name "/CATHODE_G") (class "Default")
      (node (ref "J1") (pin "5") (pinfunction "5_5") (pintype "passive"))
      (node (ref "J3") (pin "3") (pinfunction "3_3") (pintype "passive"))
      (node (ref "J5") (pin "3") (pinfunction "3_3") (pintype "passive"))
      (node (ref "LED8") (pin "C") (pinfunction "C_C") (pintype "passive"))
      (node (ref "R10") (pin "2") (pinfunction "2_2") (pintype "passive"))
    )
    (net (code "31") (name "/I2C_CLOCK") (class "Default")
      (node (ref "R15") (pin "1") (pinfunction "1_1") (pintype "passive"))
      (node (ref "U1") (pin "37") (pinfunction "RC3/SCK/SCL_37") (pintype "passive"))
      (node (ref "U4") (pin "6") (pinfunction "SCL_6") (pintype "passive"))
    )
    (net (code "32") (name "/I2C_DATA") (class "Default")
      (node (ref "R14") (pin "1") (pinfunction "1_1") (pintype "passive"))
      (node (ref "U1") (pin "42") (pinfunction "RC4/SDI/SDA_42") (pintype "passive"))
      (node (ref "U4") (pin "5") (pinfunction "SDA_5") (pintype "passive"))
    )
    (net (code "33") (name "/ICD_PGCLOCK") (class "Default")
      (node (ref "CONN2") (pin "5") (pinfunction "5_5") (pintype "passive"))
      (node (ref "U1") (pin "16") (pinfunction "RB6/KBI2/PGC_16") (pintype "passive"))
    )
    (net (code "34") (name "/ICD_PGDATA") (class "Default")
      (node (ref "CONN2") (pin "4") (pinfunction "4_4") (pintype "passive"))
      (node (ref "U1") (pin "17") (pinfunction "RB7/KBI3/PGD_17") (pintype "passive"))
    )
    (net (code "35") (name "/MSF_Signal") (class "Default")
      (node (ref "CONN1") (pin "3") (pinfunction "3_3") (pintype "passive"))
      (node (ref "U1") (pin "11") (pinfunction "RB3/AN9/CCP2_11") (pintype "passive"))
    )
    (net (code "36") (name "/RX") (class "Default")
      (node (ref "CONN1") (pin "4") (pinfunction "4_4") (pintype "passive"))
      (node (ref "U1") (pin "1") (pinfunction "RC7/RX/DT_1") (pintype "passive"))
    )
    (net (code "37") (name "/SPI_CLOCK") (class "Default")
      (node (ref "R17") (pin "1") (pinfunction "1_1") (pintype "passive"))
      (node (ref "R21") (pin "2") (pinfunction "2_2") (pintype "passive"))
      (node (ref "U1") (pin "20") (pinfunction "RA1/AN1_20") (pintype "passive"))
      (node (ref "U2") (pin "3") (pinfunction "CLK_3") (pintype "passive"))
      (node (ref "U3") (pin "2") (pinfunction "SCK_2") (pintype "passive"))
    )
    (net (code "38") (name "/SPI_DATA") (class "Default")
      (node (ref "R16") (pin "1") (pinfunction "1_1") (pintype "passive"))
      (node (ref "R20") (pin "2") (pinfunction "2_2") (pintype "passive"))
      (node (ref "U1") (pin "19") (pinfunction "RA0/AN0_19") (pintype "passive"))
      (node (ref "U2") (pin "2") (pinfunction "SDI_2") (pintype "passive"))
      (node (ref "U3") (pin "3") (pinfunction "SI_3") (pintype "passive"))
    )
    (net (code "39") (name "/SPI_LED_CS") (class "Default")
      (node (ref "R18") (pin "1") (pinfunction "1_1") (pintype "passive"))
      (node (ref "R22") (pin "2") (pinfunction "2_2") (pintype "passive"))
      (node (ref "U1") (pin "24") (pinfunction "RA5/AN4/~{SS}/HLVDIN/C2OUT_24") (pintype "passive"))
      (node (ref "U2") (pin "4") (pinfunction "LE(ED1)_4") (pintype "passive"))
    )
    (net (code "40") (name "/SPI_POT_CS") (class "Default")
      (node (ref "R19") (pin "1") (pinfunction "1_1") (pintype "passive"))
      (node (ref "R23") (pin "2") (pinfunction "2_2") (pintype "passive"))
      (node (ref "U1") (pin "21") (pinfunction "RA2/AN2/VREF-/CVREF_21") (pintype "passive"))
      (node (ref "U3") (pin "1") (pinfunction "~{CS}_1") (pintype "passive"))
    )
    (net (code "41") (name "/TX") (class "Default")
      (node (ref "CONN1") (pin "5") (pinfunction "5_5") (pintype "passive"))
      (node (ref "U1") (pin "44") (pinfunction "RC6/TX/CK_44") (pintype "passive"))
    )
    (net (code "42") (name "/W5500_CS") (class "Default")
      (node (ref "J8") (pin "1") (pinfunction "1_1") (pintype "passive"))
      (node (ref "U1") (pin "40") (pinfunction "RD2/PSP2_40") (pintype "passive"))
    )
    (net (code "43") (name "/W5500_INT") (class "Default")
      (node (ref "J8") (pin "5") (pinfunction "5_5") (pintype "passive"))
      (node (ref "U1") (pin "39") (pinfunction "RD1/PSP1_39") (pintype "passive"))
    )
    (net (code "44") (name "/W5500_MISO") (class "Default")
      (node (ref "J8") (pin "3") (pinfunction "3_3") (pintype "passive"))
      (node (ref "U1") (pin "3") (pinfunction "RD5/PSP5/P1B_3") (pintype "passive"))
    )
    (net (code "45") (name "/W5500_MOSI") (class "Default")
      (node (ref "J8") (pin "4") (pinfunction "4_4") (pintype "passive"))
      (node (ref "U1") (pin "2") (pinfunction "RD4/PSP4_2") (pintype "passive"))
    )
    (net (code "46") (name "/W5500_RST") (class "Default")
      (node (ref "J8") (pin "6") (pinfunction "6_6") (pintype "passive"))
      (node (ref "U1") (pin "38") (pinfunction "RD0/PSP0_38") (pintype "passive"))
    )
    (net (code "47") (name "/W5500_SCK") (class "Default")
      (node (ref "J8") (pin "2") (pinfunction "2_2") (pintype "passive"))
      (node (ref "U1") (pin "41") (pinfunction "RD3/PSP3_41") (pintype "passive"))
    )
    (net (code "48") (name "/~{LED_OE}") (class "Default")
      (node (ref "R2") (pin "1") (pinfunction "1_1") (pintype "passive"))
      (node (ref "U1") (pin "22") (pinfunction "RA3/AN3/VREF+_22") (pintype "passive"))
      (node (ref "U2") (pin "13") (pinfunction "~{OE(ED2)}_13") (pintype "passive"))
    )
    (net (code "49") (name "/~{MCLR}_VPP") (class "Default")
      (node (ref "CONN2") (pin "1") (pinfunction "1_1") (pintype "passive"))
      (node (ref "R1") (pin "1") (pinfunction "1_1") (pintype "passive"))
      (node (ref "U1") (pin "18") (pinfunction "~{MCLR}/VPP/RE3_18") (pintype "passive"))
    )
    (net (code "50") (name "GND") (class "Default")
      (node (ref "BATT1") (pin "-") (pinfunction "-_-") (pintype "passive"))
      (node (ref "C1") (pin "1") (pinfunction "1_1") (pintype "passive"))
      (node (ref "C2") (pin "1") (pinfunction "1_1") (pintype "passive"))
      (node (ref "C3") (pin "1") (pinfunction "1_1") (pintype "passive"))
      (node (ref "C4") (pin "1") (pinfunction "1_1") (pintype "passive"))
      (node (ref "C5") (pin "1") (pinfunction "1_1") (pintype "passive"))
      (node (ref "C6") (pin "1") (pinfunction "1_1") (pintype "passive"))
      (node (ref "C7") (pin "1") (pinfunction "1_1") (pintype "passive"))
      (node (ref "C8") (pin "1") (pinfunction "1_1") (pintype "passive"))
      (node (ref "C9") (pin "1") (pinfunction "1_1") (pintype "passive"))
      (node (ref "CONN1") (pin "1") (pinfunction "1_1") (pintype "passive"))
      (node (ref "CONN2") (pin "3") (pinfunction "3_3") (pintype "passive"))
      (node (ref "CONN3") (pin "3") (pinfunction "3_3") (pintype "passive"))
      (node (ref "CONN3") (pin "4") (pinfunction "4_4") (pintype "passive"))
      (node (ref "J7") (pin "4") (pinfunction "4_4") (pintype "passive"))
      (node (ref "J7") (pin "5") (pinfunction "5_5") (pintype "passive"))
      (node (ref "J7") (pin "6") (pinfunction "6_6") (pintype "passive"))
      (node (ref "LED3") (pin "1") (pinfunction "1_1") (pintype "passive"))
      (node (ref "PS1") (pin "2") (pinfunction "GND_2") (pintype "passive"))
      (node (ref "R13") (pin "1") (pinfunction "CCW_1") (pintype "passive"))
      (node (ref "SW1") (pin "1") (pinfunction "1_1") (pintype "passive"))
      (node (ref "SW1") (pin "2") (pinfunction "2_2") (pintype "passive"))
      (node (ref "SW1") (pin "3") (pinfunction "3_3") (pintype "passive"))
      (node (ref "SW1") (pin "4") (pinfunction "4_4") (pintype "passive"))
      (node (ref "SW2") (pin "2") (pinfunction "2_2") (pintype "passive"))
      (node (ref "SW3") (pin "2") (pinfunction "2_2") (pintype "passive"))
      (node (ref "SW4") (pin "2") (pinfunction "2_2") (pintype "passive"))
      (node (ref "SW5") (pin "2") (pinfunction "2_2") (pintype "passive"))
      (node (ref "SW6") (pin "2") (pinfunction "2_2") (pintype "passive"))
      (node (ref "U1") (pin "29") (pinfunction "VSS_2_29") (pintype "passive"))
      (node (ref "U1") (pin "6") (pinfunction "VSS_1_6") (pintype "passive"))
      (node (ref "U2") (pin "1") (pinfunction "GND_1") (pintype "passive"))
      (node (ref "U3") (pin "4") (pinfunction "VSS_4") (pintype "passive"))
      (node (ref "U3") (pin "7") (pinfunction "PB0_7") (pintype "passive"))
      (node (ref "U4") (pin "4") (pinfunction "GND_4") (pintype "passive"))
    )
    (net (code "51") (name "Net-(LED3-Pad2)") (class "Default")
      (node (ref "LED3") (pin "2") (pinfunction "2_2") (pintype "passive"))
      (node (ref "R12") (pin "1") (pinfunction "1_1") (pintype "passive"))
    )
    (net (code "52") (name "Net-(PS1-Vin)") (class "Default")
      (node (ref "C4") (pin "2") (pinfunction "2_2") (pintype "passive"))
      (node (ref "C7") (pin "2") (pinfunction "2_2") (pintype "passive"))
      (node (ref "CONN3") (pin "1") (pinfunction "1_1") (pintype "passive"))
      (node (ref "CONN3") (pin "2") (pinfunction "2_2") (pintype "passive"))
      (node (ref "PS1") (pin "1") (pinfunction "Vin_1") (pintype "input"))
    )
    (net (code "53") (name "Net-(R13-WIPER)") (class "Default")
      (node (ref "R13") (pin "2") (pinfunction "WIPER_2") (pintype "passive"))
      (node (ref "U2") (pin "15") (pinfunction "R-EXT_15") (pintype "passive"))
      (node (ref "U3") (pin "6") (pinfunction "PW0_6") (pintype "passive"))
    )
    (net (code "54") (name "Net-(R20-Pad1)") (class "Default")
      (node (ref "R20") (pin "1") (pinfunction "1_1") (pintype "passive"))
      (node (ref "SW1") (pin "8") (pinfunction "8_8") (pintype "passive"))
    )
    (net (code "55") (name "Net-(R21-Pad1)") (class "Default")
      (node (ref "R21") (pin "1") (pinfunction "1_1") (pintype "passive"))
      (node (ref "SW1") (pin "7") (pinfunction "7_7") (pintype "passive"))
    )
    (net (code "56") (name "Net-(R22-Pad1)") (class "Default")
      (node (ref "R22") (pin "1") (pinfunction "1_1") (pintype "passive"))
      (node (ref "SW1") (pin "6") (pinfunction "6_6") (pintype "passive"))
    )
    (net (code "57") (name "Net-(R23-Pad1)") (class "Default")
      (node (ref "R23") (pin "1") (pinfunction "1_1") (pintype "passive"))
      (node (ref "SW1") (pin "5") (pinfunction "5_5") (pintype "passive"))
    )
    (net (code "58") (name "Net-(U2-~{OUT0})") (class "Default")
      (node (ref "R3") (pin "1") (pinfunction "1_1") (pintype "passive"))
      (node (ref "U2") (pin "5") (pinfunction "~{OUT0}_5") (pintype "passive"))
    )
    (net (code "59") (name "Net-(U2-~{OUT1})") (class "Default")
      (node (ref "R4") (pin "1") (pinfunction "1_1") (pintype "passive"))
      (node (ref "U2") (pin "6") (pinfunction "~{OUT1}_6") (pintype "passive"))
    )
    (net (code "60") (name "Net-(U2-~{OUT2})") (class "Default")
      (node (ref "R5") (pin "1") (pinfunction "1_1") (pintype "passive"))
      (node (ref "U2") (pin "7") (pinfunction "~{OUT2}_7") (pintype "passive"))
    )
    (net (code "61") (name "Net-(U2-~{OUT3})") (class "Default")
      (node (ref "R6") (pin "1") (pinfunction "1_1") (pintype "passive"))
      (node (ref "U2") (pin "8") (pinfunction "~{OUT3}_8") (pintype "passive"))
    )
    (net (code "62") (name "Net-(U2-~{OUT4})") (class "Default")
      (node (ref "R7") (pin "1") (pinfunction "1_1") (pintype "passive"))
      (node (ref "U2") (pin "9") (pinfunction "~{OUT4}_9") (pintype "passive"))
    )
    (net (code "63") (name "Net-(U2-~{OUT5})") (class "Default")
      (node (ref "R9") (pin "1") (pinfunction "1_1") (pintype "passive"))
      (node (ref "U2") (pin "10") (pinfunction "~{OUT5}_10") (pintype "passive"))
    )
    (net (code "64") (name "Net-(U2-~{OUT6})") (class "Default")
      (node (ref "R10") (pin "1") (pinfunction "1_1") (pintype "passive"))
      (node (ref "U2") (pin "11") (pinfunction "~{OUT6}_11") (pintype "passive"))
    )
    (net (code "65") (name "Net-(U2-~{OUT7})") (class "Default")
      (node (ref "R11") (pin "1") (pinfunction "1_1") (pintype "passive"))
      (node (ref "U2") (pin "12") (pinfunction "~{OUT7}_12") (pintype "passive"))
    )
    (net (code "66") (name "Net-(U4-VBAT)") (class "Default")
      (node (ref "BATT1") (pin "+") (pinfunction "+_+") (pintype "passive"))
      (node (ref "U4") (pin "3") (pinfunction "VBAT_3") (pintype "passive"))
    )
    (net (code "67") (name "Net-(U4-X1)") (class "Default")
      (node (ref "U4") (pin "1") (pinfunction "X1_1") (pintype "passive"))
      (node (ref "XTAL1") (pin "2") (pinfunction "2_2") (pintype "passive"))
    )
    (net (code "68") (name "Net-(U4-X2)") (class "Default")
      (node (ref "U4") (pin "2") (pinfunction "X2_2") (pintype "passive"))
      (node (ref "XTAL1") (pin "1") (pinfunction "1_1") (pintype "passive"))
    )
    (net (code "69") (name "unconnected-(LED1-ANODE_1-Pad14)") (class "Default")
      (node (ref "LED1") (pin "14") (pinfunction "ANODE_1_14") (pintype "passive"))
    )
    (net (code "70") (name "unconnected-(LED1-ANODE_2-Pad11)") (class "Default")
      (node (ref "LED1") (pin "11") (pinfunction "ANODE_2_11") (pintype "passive"))
    )
    (net (code "71") (name "unconnected-(LED1-ANODE_3-Pad10)") (class "Default")
      (node (ref "LED1") (pin "10") (pinfunction "ANODE_3_10") (pintype "passive"))
    )
    (net (code "72") (name "unconnected-(LED1-ANODE_4-Pad6)") (class "Default")
      (node (ref "LED1") (pin "6") (pinfunction "ANODE_4_6") (pintype "passive"))
    )
    (net (code "73") (name "unconnected-(LED1-ANODE_COLON-Pad7)") (class "Default")
      (node (ref "LED1") (pin "7") (pinfunction "ANODE_COLON_7") (pintype "passive"))
    )
    (net (code "74") (name "unconnected-(LED1-CATHODE_A-Pad13)") (class "Default")
      (node (ref "LED1") (pin "13") (pinfunction "CATHODE_A_13") (pintype "passive"))
    )
    (net (code "75") (name "unconnected-(LED1-CATHODE_B-Pad9)") (class "Default")
      (node (ref "LED1") (pin "9") (pinfunction "CATHODE_B_9") (pintype "passive"))
    )
    (net (code "76") (name "unconnected-(LED1-CATHODE_C-Pad4)") (class "Default")
      (node (ref "LED1") (pin "4") (pinfunction "CATHODE_C_4") (pintype "passive"))
    )
    (net (code "77") (name "unconnected-(LED1-CATHODE_COLON-Pad8)") (class "Default")
      (node (ref "LED1") (pin "8") (pinfunction "CATHODE_COLON_8") (pintype "passive"))
    )
    (net (code "78") (name "unconnected-(LED1-CATHODE_D-Pad2)") (class "Default")
      (node (ref "LED1") (pin "2") (pinfunction "CATHODE_D_2") (pintype "passive"))
    )
    (net (code "79") (name "unconnected-(LED1-CATHODE_DP-Pad3)") (class "Default")
      (node (ref "LED1") (pin "3") (pinfunction "CATHODE_DP_3") (pintype "passive"))
    )
    (net (code "80") (name "unconnected-(LED1-CATHODE_E-Pad1)") (class "Default")
      (node (ref "LED1") (pin "1") (pinfunction "CATHODE_E_1") (pintype "passive"))
    )
    (net (code "81") (name "unconnected-(LED1-CATHODE_F-Pad12)") (class "Default")
      (node (ref "LED1") (pin "12") (pinfunction "CATHODE_F_12") (pintype "passive"))
    )
    (net (code "82") (name "unconnected-(LED1-CATHODE_G-Pad5)") (class "Default")
      (node (ref "LED1") (pin "5") (pinfunction "CATHODE_G_5") (pintype "passive"))
    )
    (net (code "83") (name "unconnected-(LED2-ANODE_1-Pad1)") (class "Default")
      (node (ref "LED2") (pin "1") (pinfunction "ANODE_1_1") (pintype "passive"))
    )
    (net (code "84") (name "unconnected-(LED2-ANODE_2-Pad6)") (class "Default")
      (node (ref "LED2") (pin "6") (pinfunction "ANODE_2_6") (pintype "passive"))
    )
    (net (code "85") (name "unconnected-(LED2-CATHODE_A-Pad10)") (class "Default")
      (node (ref "LED2") (pin "10") (pinfunction "CATHODE_A_10") (pintype "passive"))
    )
    (net (code "86") (name "unconnected-(LED2-CATHODE_B-Pad9)") (class "Default")
      (node (ref "LED2") (pin "9") (pinfunction "CATHODE_B_9") (pintype "passive"))
    )
    (net (code "87") (name "unconnected-(LED2-CATHODE_C-Pad8)") (class "Default")
      (node (ref "LED2") (pin "8") (pinfunction "CATHODE_C_8") (pintype "passive"))
    )
    (net (code "88") (name "unconnected-(LED2-CATHODE_D-Pad5)") (class "Default")
      (node (ref "LED2") (pin "5") (pinfunction "CATHODE_D_5") (pintype "passive"))
    )
    (net (code "89") (name "unconnected-(LED2-CATHODE_DP-Pad7)") (class "Default")
      (node (ref "LED2") (pin "7") (pinfunction "CATHODE_DP_7") (pintype "passive"))
    )
    (net (code "90") (name "unconnected-(LED2-CATHODE_E-Pad4)") (class "Default")
      (node (ref "LED2") (pin "4") (pinfunction "CATHODE_E_4") (pintype "passive"))
    )
    (net (code "91") (name "unconnected-(LED2-CATHODE_F-Pad2)") (class "Default")
      (node (ref "LED2") (pin "2") (pinfunction "CATHODE_F_2") (pintype "passive"))
    )
    (net (code "92") (name "unconnected-(LED2-CATHODE_G-Pad3)") (class "Default")
      (node (ref "LED2") (pin "3") (pinfunction "CATHODE_G_3") (pintype "passive"))
    )
    (net (code "93") (name "unconnected-(LED4-ANODE_1-Pad1)") (class "Default")
      (node (ref "LED4") (pin "1") (pinfunction "ANODE_1_1") (pintype "passive"))
    )
    (net (code "94") (name "unconnected-(LED4-ANODE_2-Pad6)") (class "Default")
      (node (ref "LED4") (pin "6") (pinfunction "ANODE_2_6") (pintype "passive"))
    )
    (net (code "95") (name "unconnected-(LED4-CATHODE_A-Pad10)") (class "Default")
      (node (ref "LED4") (pin "10") (pinfunction "CATHODE_A_10") (pintype "passive"))
    )
    (net (code "96") (name "unconnected-(LED4-CATHODE_B-Pad9)") (class "Default")
      (node (ref "LED4") (pin "9") (pinfunction "CATHODE_B_9") (pintype "passive"))
    )
    (net (code "97") (name "unconnected-(LED4-CATHODE_C-Pad8)") (class "Default")
      (node (ref "LED4") (pin "8") (pinfunction "CATHODE_C_8") (pintype "passive"))
    )
    (net (code "98") (name "unconnected-(LED4-CATHODE_D-Pad5)") (class "Default")
      (node (ref "LED4") (pin "5") (pinfunction "CATHODE_D_5") (pintype "passive"))
    )
    (net (code "99") (name "unconnected-(LED4-CATHODE_DP-Pad7)") (class "Default")
      (node (ref "LED4") (pin "7") (pinfunction "CATHODE_DP_7") (pintype "passive"))
    )
    (net (code "100") (name "unconnected-(LED4-CATHODE_E-Pad4)") (class "Default")
      (node (ref "LED4") (pin "4") (pinfunction "CATHODE_E_4") (pintype "passive"))
    )
    (net (code "101") (name "unconnected-(LED4-CATHODE_F-Pad2)") (class "Default")
      (node (ref "LED4") (pin "2") (pinfunction "CATHODE_F_2") (pintype "passive"))
    )
    (net (code "102") (name "unconnected-(LED4-CATHODE_G-Pad3)") (class "Default")
      (node (ref "LED4") (pin "3") (pinfunction "CATHODE_G_3") (pintype "passive"))
    )
    (net (code "103") (name "unconnected-(R13-CW-Pad3)") (class "Default")
      (node (ref "R13") (pin "3") (pinfunction "CW_3") (pintype "passive"))
    )
    (net (code "104") (name "unconnected-(U1-NC_1-Pad12)") (class "Default")
      (node (ref "U1") (pin "12") (pinfunction "NC_1_12") (pintype "passive"))
    )
    (net (code "105") (name "unconnected-(U1-NC_2-Pad13)") (class "Default")
      (node (ref "U1") (pin "13") (pinfunction "NC_2_13") (pintype "passive"))
    )
    (net (code "106") (name "unconnected-(U1-NC_3-Pad33)") (class "Default")
      (node (ref "U1") (pin "33") (pinfunction "NC_3_33") (pintype "passive"))
    )
    (net (code "107") (name "unconnected-(U1-NC_4-Pad34)") (class "Default")
      (node (ref "U1") (pin "34") (pinfunction "NC_4_34") (pintype "passive"))
    )
    (net (code "108") (name "unconnected-(U1-RD6{slash}PSP6{slash}P1C-Pad4)") (class "Default")
      (node (ref "U1") (pin "4") (pinfunction "RD6/PSP6/P1C_4") (pintype "passive"))
    )
    (net (code "109") (name "unconnected-(U1-RD7{slash}PSP7{slash}P1D-Pad5)") (class "Default")
      (node (ref "U1") (pin "5") (pinfunction "RD7/PSP7/P1D_5") (pintype "passive"))
    )
    (net (code "110") (name "unconnected-(U1-RE0{slash}~{RD}{slash}AN5-Pad25)") (class "Default")
      (node (ref "U1") (pin "25") (pinfunction "RE0/~{RD}/AN5_25") (pintype "passive"))
    )
    (net (code "111") (name "unconnected-(U1-RE1{slash}~{WR}{slash}AN6-Pad26)") (class "Default")
      (node (ref "U1") (pin "26") (pinfunction "RE1/~{WR}/AN6_26") (pintype "passive"))
    )
    (net (code "112") (name "unconnected-(U1-RE2{slash}~{CS}{slash}AN7-Pad27)") (class "Default")
      (node (ref "U1") (pin "27") (pinfunction "RE2/~{CS}/AN7_27") (pintype "passive"))
    )
    (net (code "113") (name "unconnected-(U2-SDO-Pad14)") (class "Default")
      (node (ref "U2") (pin "14") (pinfunction "SDO_14") (pintype "passive"))
    )
    (net (code "114") (name "unconnected-(U3-PA0-Pad5)") (class "Default")
      (node (ref "U3") (pin "5") (pinfunction "PA0_5") (pintype "passive"))
    )
  )
)
